# cardlogger.net
KiCad netlist of a schematic drawn in EAGLE
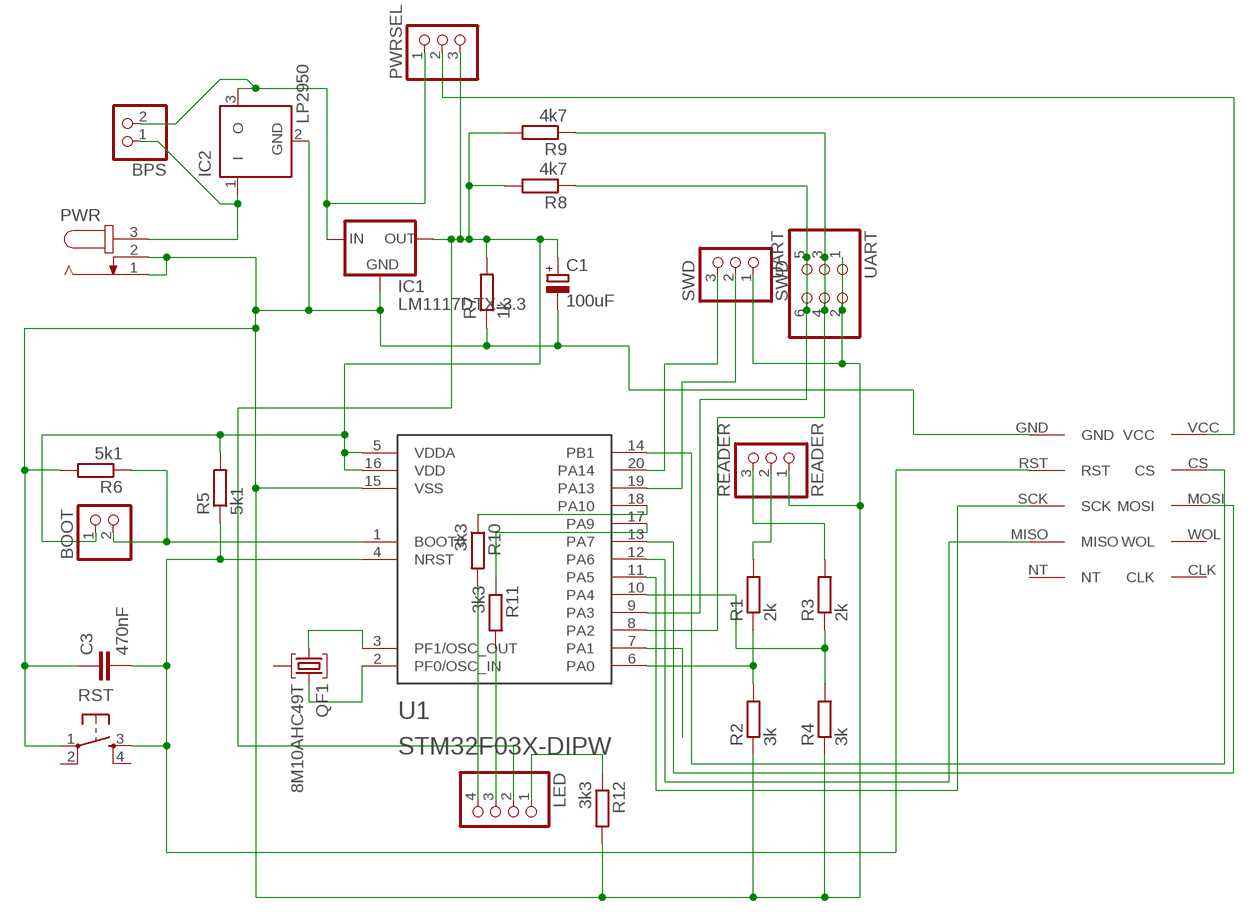
[diagram p0: schematic, sheet 1]

(export (version "E")
  (design (tool "Eeschema 10.0.6"))
  (components
    (comp (ref "BOOT")
      (value "PINHD-1X2")
      (footprint "eagle-import:1X02")
      (libsource (lib "eagle-import") (part "PINHD-1X2"))
    )
    (comp (ref "BPS")
      (value "PINHD-1X2")
      (footprint "eagle-import:1X02")
      (libsource (lib "eagle-import") (part "PINHD-1X2"))
    )
    (comp (ref "C1")
      (value "100uF")
      (footprint "eagle-import:SMC_D")
      (libsource (lib "eagle-import") (part "CPOL-EUSMCD"))
    )
    (comp (ref "C3")
      (value "470nF")
      (footprint "eagle-import:C0805")
      (libsource (lib "eagle-import") (part "C-EUC0805"))
    )
    (comp (ref "IC1")
      (value "LM1117DTX-3.3")
      (footprint "eagle-import:TO252")
      (libsource (lib "eagle-import") (part "LM1117DTX-3.3"))
    )
    (comp (ref "IC2")
      (value "LP2950")
      (footprint "eagle-import:DPACK")
      (libsource (lib "eagle-import") (part "LP2950"))
    )
    (comp (ref "LED")
      (value "PINHD-1X4")
      (footprint "eagle-import:1X04")
      (libsource (lib "eagle-import") (part "PINHD-1X4"))
    )
    (comp (ref "PWR")
      (value "JACK-PLUG0")
      (footprint "eagle-import:SPC4077")
      (libsource (lib "eagle-import") (part "JACK-PLUG0"))
    )
    (comp (ref "PWRSEL")
      (value "PINHD-1X3")
      (footprint "eagle-import:1X03")
      (libsource (lib "eagle-import") (part "PINHD-1X3"))
    )
    (comp (ref "QF1")
      (value "8M10AHC49T")
      (footprint "eagle-import:HC49U")
      (libsource (lib "eagle-import") (part "8M10AHC49T"))
    )
    (comp (ref "R1")
      (value "2k")
      (footprint "eagle-import:R1206")
      (libsource (lib "eagle-import") (part "R-EU_R1206"))
    )
    (comp (ref "R2")
      (value "3k")
      (footprint "eagle-import:R1206")
      (libsource (lib "eagle-import") (part "R-EU_R1206"))
    )
    (comp (ref "R3")
      (value "2k")
      (footprint "eagle-import:R1206")
      (libsource (lib "eagle-import") (part "R-EU_R1206"))
    )
    (comp (ref "R4")
      (value "3k")
      (footprint "eagle-import:R1206")
      (libsource (lib "eagle-import") (part "R-EU_R1206"))
    )
    (comp (ref "R5")
      (value "5k1")
      (footprint "eagle-import:R1206")
      (libsource (lib "eagle-import") (part "R-EU_R1206"))
    )
    (comp (ref "R6")
      (value "5k1")
      (footprint "eagle-import:R1206")
      (libsource (lib "eagle-import") (part "R-EU_R1206"))
    )
    (comp (ref "R7")
      (value "1k")
      (footprint "eagle-import:R1206")
      (libsource (lib "eagle-import") (part "R-EU_R1206"))
    )
    (comp (ref "R8")
      (value "4k7")
      (footprint "eagle-import:R1206")
      (libsource (lib "eagle-import") (part "R-EU_R1206"))
    )
    (comp (ref "R9")
      (value "4k7")
      (footprint "eagle-import:R1206")
      (libsource (lib "eagle-import") (part "R-EU_R1206"))
    )
    (comp (ref "R10")
      (value "3k3")
      (footprint "eagle-import:R1206")
      (libsource (lib "eagle-import") (part "R-EU_R1206"))
    )
    (comp (ref "R11")
      (value "3k3")
      (footprint "eagle-import:R1206")
      (libsource (lib "eagle-import") (part "R-EU_R1206"))
    )
    (comp (ref "R12")
      (value "3k3")
      (footprint "eagle-import:R1206")
      (libsource (lib "eagle-import") (part "R-EU_R1206"))
    )
    (comp (ref "READER")
      (value "READER")
      (footprint "eagle-import:1X03")
      (libsource (lib "eagle-import") (part "PINHD-1X3"))
    )
    (comp (ref "RST")
      (value "TAC_SWITCHPTH")
      (footprint "eagle-import:TACTILE-PTH")
      (libsource (lib "eagle-import") (part "TAC_SWITCHPTH"))
    )
    (comp (ref "SWD")
      (value "SWD")
      (footprint "eagle-import:1X03")
      (libsource (lib "eagle-import") (part "PINHD-1X3"))
    )
    (comp (ref "U$1")
      (value "ENC28J60")
      (footprint "eagle-import:ENC28J60")
      (libsource (lib "eagle-import") (part "ENC28J60"))
    )
    (comp (ref "U1")
      (value "STM32F03X-DIPW")
      (footprint "eagle-import:DIP20W")
      (libsource (lib "eagle-import") (part "STM32F03X-DIPW"))
    )
    (comp (ref "UART")
      (value "UART")
      (footprint "eagle-import:2X03")
      (libsource (lib "eagle-import") (part "PINHD-2X3"))
    )
  )
  (nets
    (net (code "1") (name "Net-(IC1-GND)") (class "Default")
      (node (ref "C1") (pin "-") (pinfunction "-_-") (pintype "passive"))
      (node (ref "C3") (pin "1") (pinfunction "1_1") (pintype "passive"))
      (node (ref "IC1") (pin "1") (pinfunction "GND_1") (pintype "input"))
      (node (ref "IC2") (pin "2") (pinfunction "GND_2") (pintype "power_in"))
      (node (ref "PWR") (pin "1") (pinfunction "1_1") (pintype "passive"))
      (node (ref "PWR") (pin "2") (pinfunction "2_2") (pintype "passive"))
      (node (ref "R12") (pin "2") (pinfunction "2_2") (pintype "passive"))
      (node (ref "R2") (pin "1") (pinfunction "1_1") (pintype "passive"))
      (node (ref "R4") (pin "1") (pinfunction "1_1") (pintype "passive"))
      (node (ref "R6") (pin "2") (pinfunction "2_2") (pintype "passive"))
      (node (ref "R7") (pin "1") (pinfunction "1_1") (pintype "passive"))
      (node (ref "READER") (pin "1") (pinfunction "1_1") (pintype "passive"))
      (node (ref "RST") (pin "1") (pinfunction "1_1") (pintype "passive"))
      (node (ref "SWD") (pin "1") (pinfunction "1_1") (pintype "passive"))
      (node (ref "U$1") (pin "GND") (pinfunction "GND_GND") (pintype "bidirectional"))
      (node (ref "U1") (pin "15") (pinfunction "VSS_15") (pintype "bidirectional"))
      (node (ref "UART") (pin "1") (pinfunction "1_1") (pintype "passive"))
      (node (ref "UART") (pin "2") (pinfunction "2_2") (pintype "passive"))
    )
    (net (code "2") (name "Net-(IC1-IN)") (class "Default")
      (node (ref "BPS") (pin "2") (pinfunction "2_2") (pintype "passive"))
      (node (ref "IC1") (pin "2") (pinfunction "IN_2") (pintype "input"))
      (node (ref "IC2") (pin "3") (pinfunction "O_3") (pintype "input"))
      (node (ref "PWRSEL") (pin "1") (pinfunction "1_1") (pintype "passive"))
    )
    (net (code "3") (name "Net-(IC1-OUT)") (class "Default")
      (node (ref "BOOT") (pin "1") (pinfunction "1_1") (pintype "passive"))
      (node (ref "C1") (pin "+") (pinfunction "+_+") (pintype "passive"))
      (node (ref "IC1") (pin "TAB") (pinfunction "OUT_TAB") (pintype "passive"))
      (node (ref "LED") (pin "2") (pinfunction "2_2") (pintype "passive"))
      (node (ref "PWRSEL") (pin "3") (pinfunction "3_3") (pintype "passive"))
      (node (ref "R5") (pin "2") (pinfunction "2_2") (pintype "passive"))
      (node (ref "R7") (pin "2") (pinfunction "2_2") (pintype "passive"))
      (node (ref "R8") (pin "2") (pinfunction "2_2") (pintype "passive"))
      (node (ref "R9") (pin "2") (pinfunction "2_2") (pintype "passive"))
      (node (ref "U1") (pin "16") (pinfunction "VDD_16") (pintype "bidirectional"))
      (node (ref "U1") (pin "5") (pinfunction "VDDA_5") (pintype "bidirectional"))
    )
    (net (code "4") (name "Net-(IC2-I)") (class "Default")
      (node (ref "BPS") (pin "1") (pinfunction "1_1") (pintype "passive"))
      (node (ref "IC2") (pin "1") (pinfunction "I_1") (pintype "input"))
      (node (ref "PWR") (pin "3") (pinfunction "3_3") (pintype "passive"))
    )
    (net (code "5") (name "Net-(LED-Pad1)") (class "Default")
      (node (ref "LED") (pin "1") (pinfunction "1_1") (pintype "passive"))
      (node (ref "R12") (pin "1") (pinfunction "1_1") (pintype "passive"))
    )
    (net (code "6") (name "Net-(LED-Pad3)") (class "Default")
      (node (ref "LED") (pin "3") (pinfunction "3_3") (pintype "passive"))
      (node (ref "R11") (pin "2") (pinfunction "2_2") (pintype "passive"))
    )
    (net (code "7") (name "Net-(LED-Pad4)") (class "Default")
      (node (ref "LED") (pin "4") (pinfunction "4_4") (pintype "passive"))
      (node (ref "R10") (pin "2") (pinfunction "2_2") (pintype "passive"))
    )
    (net (code "8") (name "Net-(PWRSEL-Pad2)") (class "Default")
      (node (ref "PWRSEL") (pin "2") (pinfunction "2_2") (pintype "passive"))
      (node (ref "U$1") (pin "VCC") (pinfunction "VCC_VCC") (pintype "bidirectional"))
    )
    (net (code "9") (name "Net-(R1-Pad2)") (class "Default")
      (node (ref "R1") (pin "2") (pinfunction "2_2") (pintype "passive"))
      (node (ref "READER") (pin "2") (pinfunction "2_2") (pintype "passive"))
    )
    (net (code "10") (name "Net-(R3-Pad2)") (class "Default")
      (node (ref "R3") (pin "2") (pinfunction "2_2") (pintype "passive"))
      (node (ref "READER") (pin "3") (pinfunction "3_3") (pintype "passive"))
    )
    (net (code "11") (name "Net-(U1-BOOT0)") (class "Default")
      (node (ref "BOOT") (pin "2") (pinfunction "2_2") (pintype "passive"))
      (node (ref "R6") (pin "1") (pinfunction "1_1") (pintype "passive"))
      (node (ref "U1") (pin "1") (pinfunction "BOOT0_1") (pintype "bidirectional"))
    )
    (net (code "12") (name "Net-(U1-NRST)") (class "Default")
      (node (ref "C3") (pin "2") (pinfunction "2_2") (pintype "passive"))
      (node (ref "R5") (pin "1") (pinfunction "1_1") (pintype "passive"))
      (node (ref "RST") (pin "3") (pinfunction "3_3") (pintype "passive"))
      (node (ref "U$1") (pin "RST") (pinfunction "RST_RST") (pintype "bidirectional"))
      (node (ref "U1") (pin "4") (pinfunction "NRST_4") (pintype "bidirectional"))
    )
    (net (code "13") (name "Net-(U1-PA0)") (class "Default")
      (node (ref "R1") (pin "1") (pinfunction "1_1") (pintype "passive"))
      (node (ref "R2") (pin "2") (pinfunction "2_2") (pintype "passive"))
      (node (ref "U1") (pin "6") (pinfunction "PA0_6") (pintype "bidirectional"))
    )
    (net (code "14") (name "Net-(U1-PA2)") (class "Default")
      (node (ref "R9") (pin "1") (pinfunction "1_1") (pintype "passive"))
      (node (ref "U1") (pin "8") (pinfunction "PA2_8") (pintype "bidirectional"))
      (node (ref "UART") (pin "3") (pinfunction "3_3") (pintype "passive"))
      (node (ref "UART") (pin "4") (pinfunction "4_4") (pintype "passive"))
    )
    (net (code "15") (name "Net-(U1-PA3)") (class "Default")
      (node (ref "R8") (pin "1") (pinfunction "1_1") (pintype "passive"))
      (node (ref "U1") (pin "9") (pinfunction "PA3_9") (pintype "bidirectional"))
      (node (ref "UART") (pin "5") (pinfunction "5_5") (pintype "passive"))
      (node (ref "UART") (pin "6") (pinfunction "6_6") (pintype "passive"))
    )
    (net (code "16") (name "Net-(U1-PA4)") (class "Default")
      (node (ref "R3") (pin "1") (pinfunction "1_1") (pintype "passive"))
      (node (ref "R4") (pin "2") (pinfunction "2_2") (pintype "passive"))
      (node (ref "U1") (pin "10") (pinfunction "PA4_10") (pintype "bidirectional"))
    )
    (net (code "17") (name "Net-(U1-PA5)") (class "Default")
      (node (ref "U$1") (pin "SCK") (pinfunction "SCK_SCK") (pintype "bidirectional"))
      (node (ref "U1") (pin "11") (pinfunction "PA5_11") (pintype "bidirectional"))
    )
    (net (code "18") (name "Net-(U1-PA6)") (class "Default")
      (node (ref "U$1") (pin "MISO") (pinfunction "MISO_MISO") (pintype "bidirectional"))
      (node (ref "U1") (pin "12") (pinfunction "PA6_12") (pintype "bidirectional"))
    )
    (net (code "19") (name "Net-(U1-PA7)") (class "Default")
      (node (ref "U$1") (pin "MOSI") (pinfunction "MOSI_MOSI") (pintype "bidirectional"))
      (node (ref "U1") (pin "13") (pinfunction "PA7_13") (pintype "bidirectional"))
    )
    (net (code "20") (name "Net-(U1-PA9)") (class "Default")
      (node (ref "R11") (pin "1") (pinfunction "1_1") (pintype "passive"))
      (node (ref "U1") (pin "17") (pinfunction "PA9_17") (pintype "bidirectional"))
    )
    (net (code "21") (name "Net-(U1-PA10)") (class "Default")
      (node (ref "R10") (pin "1") (pinfunction "1_1") (pintype "passive"))
      (node (ref "U1") (pin "18") (pinfunction "PA10_18") (pintype "bidirectional"))
    )
    (net (code "22") (name "Net-(U1-PA13)") (class "Default")
      (node (ref "SWD") (pin "2") (pinfunction "2_2") (pintype "passive"))
      (node (ref "U1") (pin "19") (pinfunction "PA13_19") (pintype "bidirectional"))
    )
    (net (code "23") (name "Net-(U1-PA14)") (class "Default")
      (node (ref "SWD") (pin "3") (pinfunction "3_3") (pintype "passive"))
      (node (ref "U1") (pin "20") (pinfunction "PA14_20") (pintype "bidirectional"))
    )
    (net (code "24") (name "Net-(U1-PB1)") (class "Default")
      (node (ref "U$1") (pin "CS") (pinfunction "CS_CS") (pintype "bidirectional"))
      (node (ref "U1") (pin "14") (pinfunction "PB1_14") (pintype "bidirectional"))
    )
    (net (code "25") (name "Net-(U1-PF0{slash}OSC_IN)") (class "Default")
      (node (ref "QF1") (pin "3") (pinfunction "3_3") (pintype "passive"))
      (node (ref "U1") (pin "2") (pinfunction "PF0/OSC_IN_2") (pintype "bidirectional"))
    )
    (net (code "26") (name "Net-(U1-PF1{slash}OSC_OUT)") (class "Default")
      (node (ref "QF1") (pin "1") (pinfunction "1_1") (pintype "passive"))
      (node (ref "U1") (pin "3") (pinfunction "PF1/OSC_OUT_3") (pintype "bidirectional"))
    )
    (net (code "27") (name "unconnected-(QF1-Pad2)") (class "Default")
      (node (ref "QF1") (pin "2") (pinfunction "2_2") (pintype "passive"))
    )
    (net (code "28") (name "unconnected-(RST-Pad2)") (class "Default")
      (node (ref "RST") (pin "2") (pinfunction "2_2") (pintype "passive"))
    )
    (net (code "29") (name "unconnected-(RST-Pad4)") (class "Default")
      (node (ref "RST") (pin "4") (pinfunction "4_4") (pintype "passive"))
    )
    (net (code "30") (name "unconnected-(U$1-PadCLK)") (class "Default")
      (node (ref "U$1") (pin "CLK") (pinfunction "CLK_CLK") (pintype "bidirectional"))
    )
    (net (code "31") (name "unconnected-(U$1-PadNT)") (class "Default")
      (node (ref "U$1") (pin "NT") (pinfunction "NT_NT") (pintype "bidirectional"))
    )
    (net (code "32") (name "unconnected-(U$1-PadWOL)") (class "Default")
      (node (ref "U$1") (pin "WOL") (pinfunction "WOL_WOL") (pintype "bidirectional"))
    )
    (net (code "33") (name "unconnected-(U1-PA1-Pad7)") (class "Default")
      (node (ref "U1") (pin "7") (pinfunction "PA1_7") (pintype "bidirectional"))
    )
  )
)
